# Mini_Multi_Function_Device.net
KiCad netlist of a schematic drawn in Altium Designer
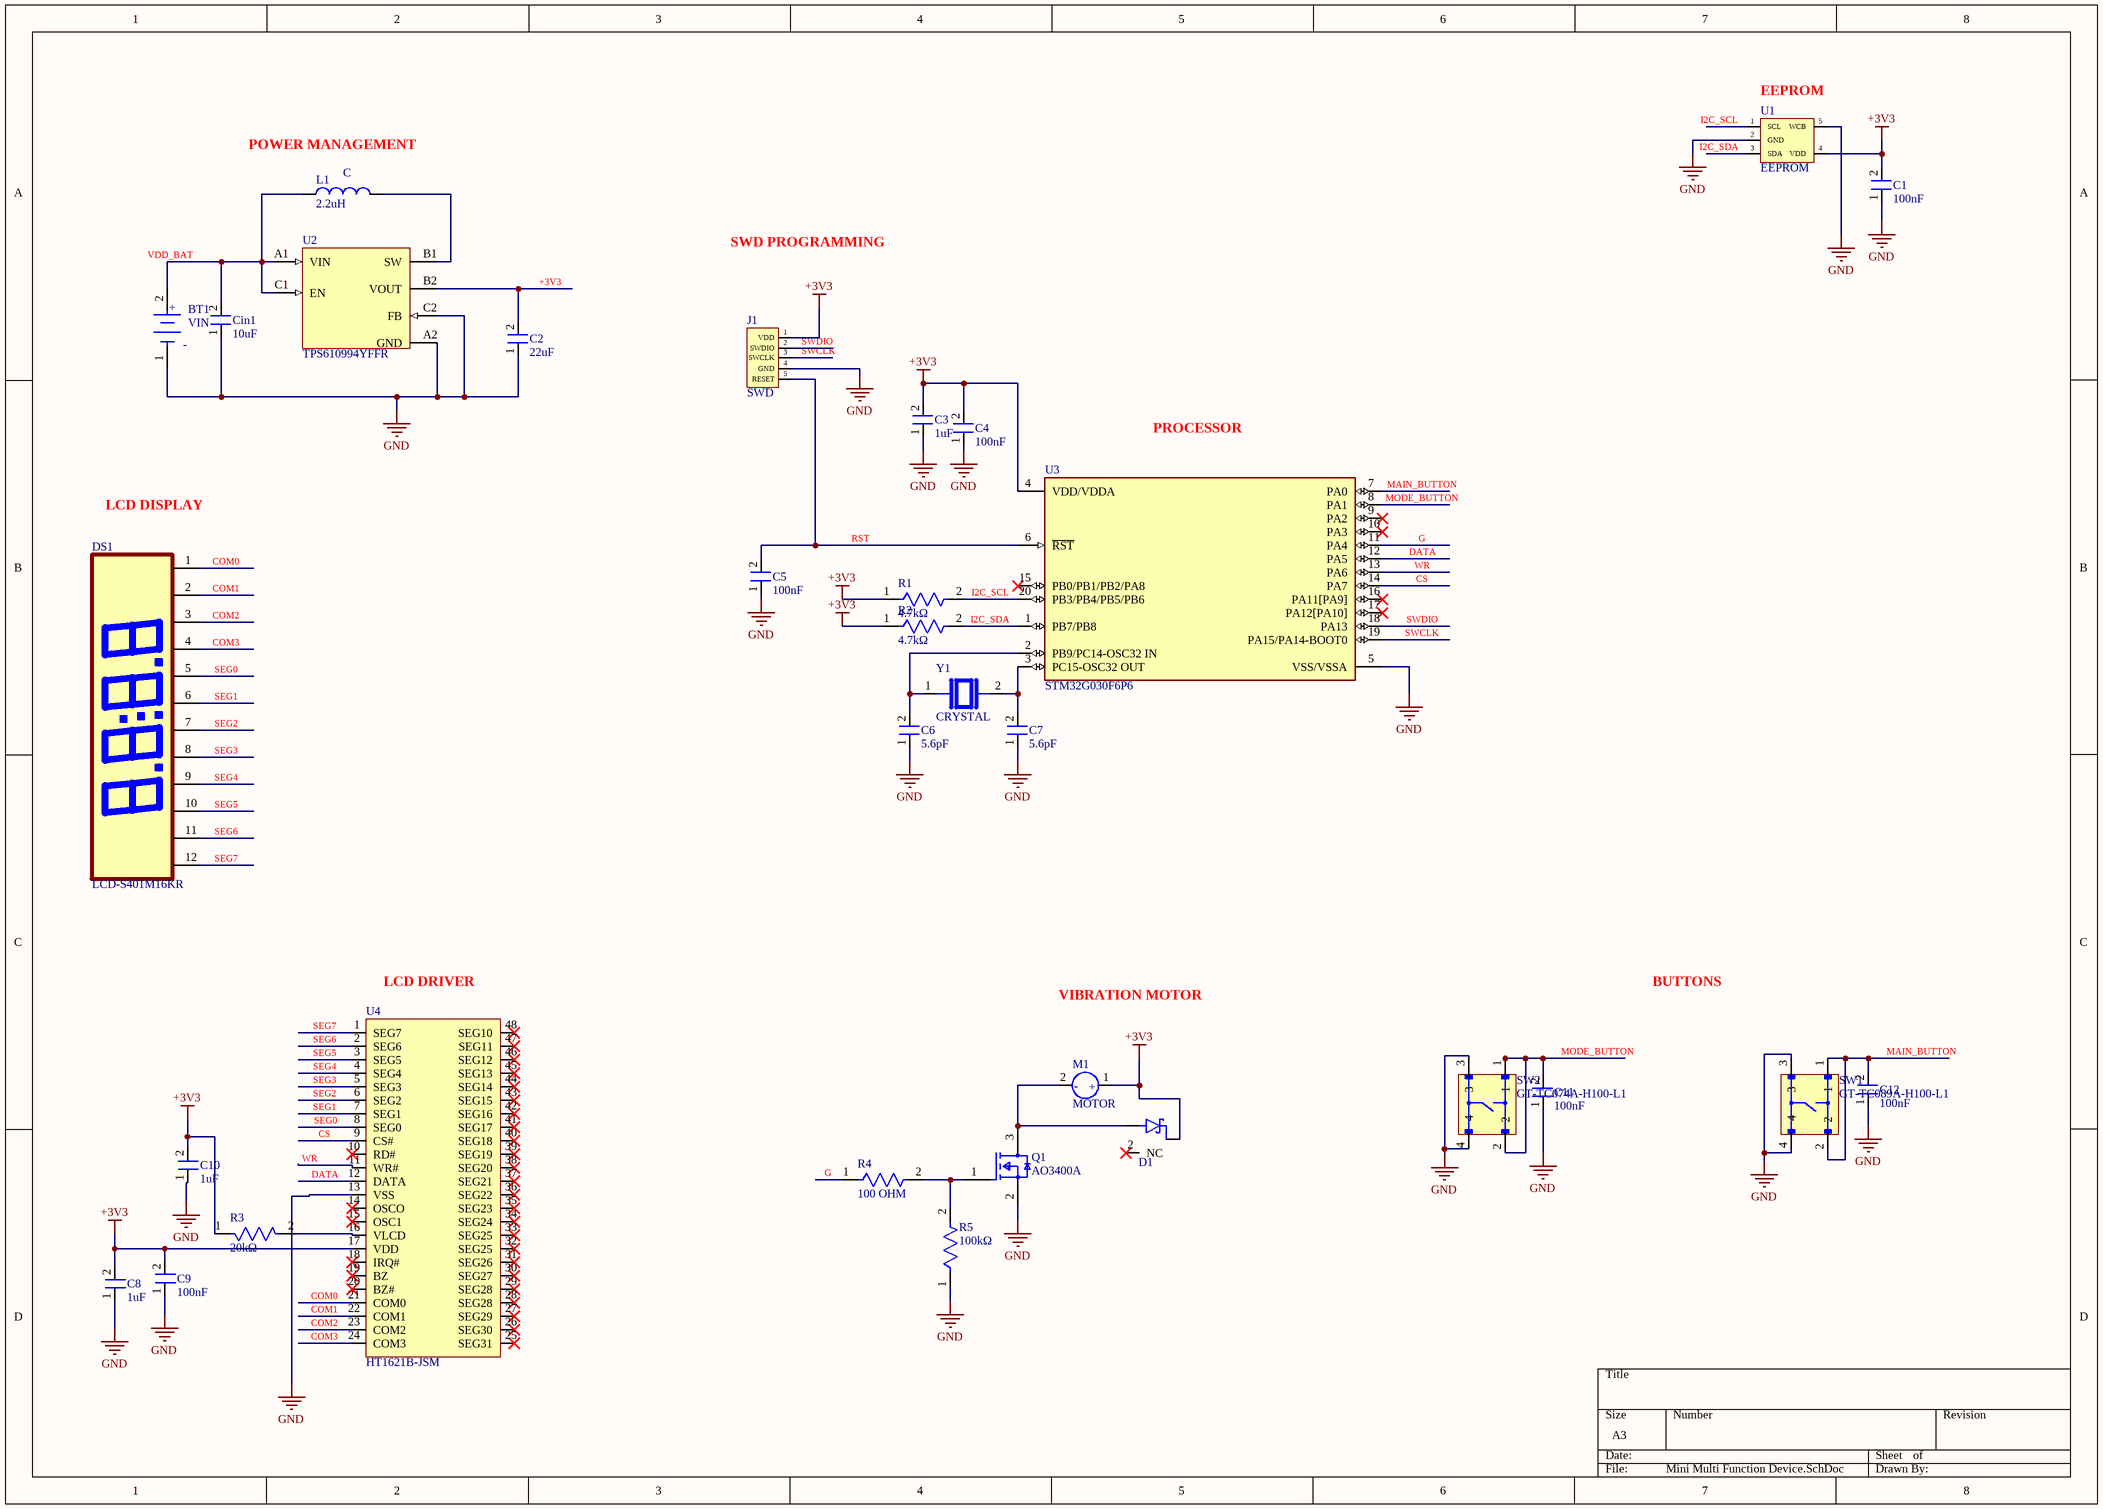
[diagram p0: Mini Multi Function Device.SchDoc]

(export (version "E")
  (design (tool "Eeschema 10.0.6"))
  (components
    (comp (ref "BT1")
      (value "VIN")
      (footprint "FP-3034-MFG")
      (description "Retainer 1 Button cell Ø20.0mm 2020，2025，2032 PCBinstall，SMD mount 4.06mm(height)")
      (fields (field (name "MANUFACTURER") "Keystone") (field (name "MANUFACTURER PART NUMBER") "3034"))
      (libsource (lib "Mini Multi Function Device") (part "3034"))
    )
    (comp (ref "C1")
      (value "100nF")
      (footprint "CAPACITOR")
      (description "Ceramic Capacitor, Ceramic, 10V, 5% +Tol, 5% -Tol, X5R, 15% TC, 0.1uF, Surface Mount, 0402")
      (fields
        (field (name "MANUFACTURER") "Yageo Group")
        (field (name "MANUFACTURER PART NUMBER") "CC0402JRX5R6BB104")
      )
      (libsource (lib "Mini Multi Function Device") (part "CC0402JRX5R6BB104"))
    )
    (comp (ref "C2")
      (value "22uF")
      (footprint "CAPACITOR_0805")
      (description "22uF 6.3V X5R ±20% 0805 Multilayer Ceramic Capacitors MLCC - SMD/SMT ROHS")
      (fields (field (name "LCSC PART") "C396739") (field (name "MANUFACTURER") "Walsin Tech Corp"))
      (libsource (lib "Mini Multi Function Device") (part "0805X226M6R3CT"))
    )
    (comp (ref "C3")
      (value "1uF")
      (footprint "CAPACITOR")
      (description "16V 1uF X5R 卤10% 0402 Multilayer Ceramic Capacitors MLCC - SMD/SMT ROHS")
      (fields
        (field (name "MANUFACTURER") "Samsung Electro-Mechanics")
        (field (name "MANUFACTURER PART NUMBER") "CL05A105KO5NNNC")
      )
      (libsource (lib "Mini Multi Function Device") (part "CL05A105KO5NNNC"))
    )
    (comp (ref "C4")
      (value "100nF")
      (footprint "CAPACITOR")
      (description "FCC0402B104K160AT 100nF ±10% 16V Ceramic Capacitor X7R 0402 Ceramic Capacitors  100nF   16V 10%")
      (fields (field (name "LCSC PART") "C5137468") (field (name "MANUFACTURER") "FOJAN"))
      (libsource (lib "Mini Multi Function Device") (part "FCC0402B104K160AT"))
    )
    (comp (ref "C5")
      (value "100nF")
      (footprint "CAPACITOR")
      (description "Ceramic Capacitor, Ceramic, 10V, 5% +Tol, 5% -Tol, X5R, 15% TC, 0.1uF, Surface Mount, 0402")
      (fields
        (field (name "MANUFACTURER") "Yageo Group")
        (field (name "MANUFACTURER PART NUMBER") "CC0402JRX5R6BB104")
      )
      (libsource (lib "Mini Multi Function Device") (part "CC0402JRX5R6BB104"))
    )
    (comp (ref "C6")
      (value "5.6pF")
      (footprint "CAPACITOR")
      (description "10V 5.6pF C0G 0402 Multilayer Ceramic Capacitors MLCC - SMD/SMT ROHS")
      (fields
        (field (name "LCSC PART") "C285041")
        (field (name "MANUFACTURER") "FH (Guangdong Fenghua Advanced Tech)")
      )
      (libsource (lib "Mini Multi Function Device") (part "0402CG5R6C100NT"))
    )
    (comp (ref "C7")
      (value "5.6pF")
      (footprint "CAPACITOR")
      (description "10V 5.6pF C0G 0402 Multilayer Ceramic Capacitors MLCC - SMD/SMT ROHS")
      (fields
        (field (name "LCSC PART") "C285041")
        (field (name "MANUFACTURER") "FH (Guangdong Fenghua Advanced Tech)")
      )
      (libsource (lib "Mini Multi Function Device") (part "0402CG5R6C100NT"))
    )
    (comp (ref "C8")
      (value "1uF")
      (footprint "CAPACITOR")
      (description "16V 1uF X5R 卤10% 0402 Multilayer Ceramic Capacitors MLCC - SMD/SMT ROHS")
      (fields
        (field (name "MANUFACTURER") "Samsung Electro-Mechanics")
        (field (name "MANUFACTURER PART NUMBER") "CL05A105KO5NNNC")
      )
      (libsource (lib "Mini Multi Function Device") (part "CL05A105KO5NNNC"))
    )
    (comp (ref "C9")
      (value "100nF")
      (footprint "CAPACITOR")
      (description "Ceramic Capacitor, Ceramic, 10V, 5% +Tol, 5% -Tol, X5R, 15% TC, 0.1uF, Surface Mount, 0402")
      (fields
        (field (name "MANUFACTURER") "Yageo Group")
        (field (name "MANUFACTURER PART NUMBER") "CC0402JRX5R6BB104")
      )
      (libsource (lib "Mini Multi Function Device") (part "CC0402JRX5R6BB104"))
    )
    (comp (ref "C10")
      (value "1uF")
      (footprint "CAPACITOR")
      (description "16V 1uF X5R 卤10% 0402 Multilayer Ceramic Capacitors MLCC - SMD/SMT ROHS")
      (fields
        (field (name "MANUFACTURER") "Samsung Electro-Mechanics")
        (field (name "MANUFACTURER PART NUMBER") "CL05A105KO5NNNC")
      )
      (libsource (lib "Mini Multi Function Device") (part "CL05A105KO5NNNC"))
    )
    (comp (ref "C11")
      (value "100nF")
      (footprint "CAPACITOR")
      (description "FCC0402B104K160AT 100nF ±10% 16V Ceramic Capacitor X7R 0402 Ceramic Capacitors  100nF   16V 10%")
      (fields (field (name "LCSC PART") "C5137468") (field (name "MANUFACTURER") "FOJAN"))
      (libsource (lib "Mini Multi Function Device") (part "FCC0402B104K160AT"))
    )
    (comp (ref "C12")
      (value "100nF")
      (footprint "CAPACITOR")
      (description "FCC0402B104K160AT 100nF ±10% 16V Ceramic Capacitor X7R 0402 Ceramic Capacitors  100nF   16V 10%")
      (fields (field (name "LCSC PART") "C5137468") (field (name "MANUFACTURER") "FOJAN"))
      (libsource (lib "Mini Multi Function Device") (part "FCC0402B104K160AT"))
    )
    (comp (ref "Cin1")
      (value "10uF")
      (footprint "CAPACITOR_0805")
      (description "10V 10uF X5R ±10% 0805 Multilayer Ceramic Capacitors MLCC - SMD/SMT ROHS")
      (fields (field (name "LCSC PART") "C77073") (field (name "MANUFACTURER") "Murata Electronics"))
      (libsource (lib "Mini Multi Function Device") (part "GRM21BR61A106KE19L"))
    )
    (comp (ref "D1")
      (value "BAT54")
      (footprint "SOT95P240X120-3N")
      (description "Diode Schottky 30V 0.2A Automotive 3-Pin SOT-23")
      (fields (field (name "MANUFACTURER") "Diodes Inc.") (field (name "LCSC PART") "C7528904"))
      (libsource (lib "Mini Multi Function Device") (part "BAT54"))
    )
    (comp (ref "DS1")
      (value "LCD-S401M16KR")
      (footprint "LCD-S401M16KR")
      (description "LCD Numeric Display Modules 4 Digit 0.17 7 Seg Reflective")
      (fields (field (name "MANUFACTURER") "Lumex") (field (name "LCSC PART") "C17355221"))
      (libsource (lib "Mini Multi Function Device") (part "LCD-S401M16KR"))
    )
    (comp (ref "J1")
      (value "SWD")
      (footprint "SWD_HEADER")
      (libsource (lib "Mini Multi Function Device") (part "SWD_HEADER"))
    )
    (comp (ref "L1")
      (value "2.2uH")
      (footprint "INDC2520X100N")
      (description "Inductor Power Chip Shielded Multi-Layer 2.2uH 20% 1MHz Ferrite 1.3A 0.1Ohm DCR 1008 T/R")
      (fields
        (field (name "MANUFACTURER") "Murata")
        (field (name "MANUFACTURER PART NUMBER") "LQM2HPN2R2MG0L")
      )
      (libsource (lib "Mini Multi Function Device") (part "LQM2HPN2R2MG0L"))
    )
    (comp (ref "M1")
      (value "MOTOR")
      (footprint "VCLP1020B002L")
      (description "Vibration Coin 3V Low Curr 0.75G")
      (fields
        (field (name "MANUFACTURER") "Vybronics")
        (field (name "MANUFACTURER PART NUMBER") "VCLP1020B002L")
      )
      (libsource (lib "Mini Multi Function Device") (part "VCLP1020B002L"))
    )
    (comp (ref "Q1")
      (value "AO3400A")
      (footprint "FP-SOT23-MFG")
      (description "Trans MOSFET N-CH 30V 5.7A 3-Pin SOT-23")
      (fields (field (name "MANUFACTURER") "Alpha & Omega Semiconductor") (field (name "LCSC PART") "C20917"))
      (libsource (lib "Mini Multi Function Device") (part "AO3400A"))
    )
    (comp (ref "R1")
      (value "4.7kΩ")
      (footprint "RESISTOR")
      (description "-55℃~+125℃ 30V 4.7kΩ 62.5mW ±5% ±50ppm/℃ 0402 Chip Resistor - Surface Mount ROHS")
      (fields (field (name "LCSC PART") "C54974059") (field (name "MANUFACTURER") "SIE"))
      (libsource (lib "Mini Multi Function Device") (part "CRF0402R472JN"))
    )
    (comp (ref "R2")
      (value "4.7kΩ")
      (footprint "RESISTOR")
      (description "-55℃~+125℃ 30V 4.7kΩ 62.5mW ±5% ±50ppm/℃ 0402 Chip Resistor - Surface Mount ROHS")
      (fields (field (name "LCSC PART") "C54974059") (field (name "MANUFACTURER") "SIE"))
      (libsource (lib "Mini Multi Function Device") (part "CRF0402R472JN"))
    )
    (comp (ref "R3")
      (value "20kΩ")
      (footprint "RESISTOR")
      (fields
        (field (name "LCSC PART") "C319759")
        (field (name "MANUFACTURER") "Viking Tech")
        (field (name "MANUFACTURER PART NUMBER") "AR02DTD2002")
      )
      (libsource (lib "Mini Multi Function Device") (part "AR02DTD2002"))
    )
    (comp (ref "R4")
      (value "100 OHM")
      (footprint "RESISTOR")
      (description "Res Thick Film 0402 100 Ohm 5% 0.063W(1/16W) ±100ppm/C Pad SMD T/R Automotive AEC-Q200")
      (fields
        (field (name "MANUFACTURER") "Yageo Group")
        (field (name "MANUFACTURER PART NUMBER") "AC0402JR-07100RL")
      )
      (libsource (lib "Mini Multi Function Device") (part "AC0402JR-07100RL"))
    )
    (comp (ref "R5")
      (value "100kΩ")
      (footprint "RESISTOR")
      (description "62.5mW Thick Film Resistors 50V ±100ppm/℃ ±5% 100kΩ 0402 Chip Resistor - Surface Mount ROHS")
      (fields
        (field (name "MANUFACTURER") "Yageo Group")
        (field (name "MANUFACTURER PART NUMBER") "RC0402JR-07100KL")
      )
      (libsource (lib "Mini Multi Function Device") (part "RC0402JR-07100KL"))
    )
    (comp (ref "SW1")
      (value "GT-TC089A-H100-L1")
      (footprint "SW-SMD_4P-L6.0-W6.0-P4.50-LS8.5")
      (fields (field (name "LCSC PART") "C843652") (field (name "MANUFACTURER") "G-Switch"))
      (libsource (lib "Mini Multi Function Device") (part "GT-TC089A-H100-L1"))
    )
    (comp (ref "SW2")
      (value "GT-TC074A-H100-L1")
      (footprint "SW-SMD_4P-L4.5-W4.5-P3.00-LS7.5")
      (fields (field (name "LCSC PART") "C963232") (field (name "MANUFACTURER") "G-Switch"))
      (libsource (lib "Mini Multi Function Device") (part "GT-TC074A-H100-L1"))
    )
    (comp (ref "U1")
      (value "EEPROM")
      (footprint "AT24C02C-STUM-TQN")
      (description "SOT-23-5 EEPROM ROHS")
      (fields (field (name "LCSC PART") "C53432858") (field (name "MANUFACTURER") "QNH"))
      (libsource (lib "Mini Multi Function Device") (part "AT24C02C-STUM-TQN"))
    )
    (comp (ref "U2")
      (value "TPS610994YFFR")
      (footprint "BGA6N40P3X2_122X88X62N")
      (description "0.7Vin Synchronous Boost Converter with 800 nA Ultra-Low Quiescent Current 6-DSBGA -40 to 85")
      (fields (field (name "MANUFACTURER") "Texas Instruments") (field (name "LCSC PART") "C2650335"))
      (libsource (lib "Mini Multi Function Device") (part "TPS610994YFFR"))
    )
    (comp (ref "U3")
      (value "STM32G030F6P6")
      (footprint "FP-TSSOP20-YA-MFG")
      (description "Microcontroller 32-bit ARM Cortex-M0+ RISC 32KB Flash 3.3V 20-Pin TSSOP Tray")
      (fields (field (name "MANUFACTURER") "STMicroelectronics") (field (name "LCSC PART") "C724040"))
      (libsource (lib "Mini Multi Function Device") (part "STM32G030F6P6"))
    )
    (comp (ref "U4")
      (value "HT1621B-JSM")
      (footprint "HT1621B-JSM")
      (fields (field (name "LCSC PART") "C18190086") (field (name "MANUFACTURER") "JSMSEMI"))
      (libsource (lib "Mini Multi Function Device") (part "HT1621B-JSM"))
    )
    (comp (ref "Y1")
      (value "CRYSTAL")
      (footprint "OSC-SMD_L3.2-W1.5")
      (description "-40℃~+85℃ 12.5pF 32.768kHz 70kΩ SMD crystal oscillator ±20ppm ±30ppm SMD3215-2P Crystals ROHS")
      (fields (field (name "LCSC PART") "C620155") (field (name "MANUFACTURER") "YXC Crystal Oscillators"))
      (libsource (lib "Mini Multi Function Device") (part "X321532768KGD2SI"))
    )
  )
  (nets
    (net (code "1") (name "+3V3") (class "Default")
      (node (ref "C1") (pin "2") (pinfunction "3_2") (pintype "passive"))
      (node (ref "C10") (pin "2") (pinfunction "3_2") (pintype "passive"))
      (node (ref "C2") (pin "2") (pinfunction "3_2") (pintype "passive"))
      (node (ref "C3") (pin "2") (pinfunction "3_2") (pintype "passive"))
      (node (ref "C4") (pin "2") (pinfunction "3_2") (pintype "passive"))
      (node (ref "C8") (pin "2") (pinfunction "3_2") (pintype "passive"))
      (node (ref "C9") (pin "2") (pinfunction "3_2") (pintype "passive"))
      (node (ref "D1") (pin "3") (pinfunction "3_3") (pintype "passive"))
      (node (ref "J1") (pin "1") (pinfunction "VDD_1") (pintype "passive"))
      (node (ref "M1") (pin "1") (pinfunction "1_1") (pintype "passive"))
      (node (ref "R1") (pin "1") (pinfunction "1_1") (pintype "passive"))
      (node (ref "R2") (pin "1") (pinfunction "1_1") (pintype "passive"))
      (node (ref "R3") (pin "1") (pinfunction "1_1") (pintype "passive"))
      (node (ref "U1") (pin "4") (pinfunction "VDD_4") (pintype "passive"))
      (node (ref "U2") (pin "B2") (pinfunction "VOUT_B2") (pintype "passive"))
      (node (ref "U3") (pin "4") (pinfunction "VDD/VDDA_4") (pintype "power_in"))
      (node (ref "U4") (pin "17") (pinfunction "VDD_17") (pintype "open_collector"))
    )
    (net (code "2") (name "/COM0") (class "Default")
      (node (ref "DS1") (pin "1") (pinfunction "P$1_1") (pintype "passive"))
      (node (ref "U4") (pin "21") (pinfunction "COM0_21") (pintype "open_collector"))
    )
    (net (code "3") (name "/COM1") (class "Default")
      (node (ref "DS1") (pin "2") (pinfunction "P$2_2") (pintype "passive"))
      (node (ref "U4") (pin "22") (pinfunction "COM1_22") (pintype "open_collector"))
    )
    (net (code "4") (name "/COM2") (class "Default")
      (node (ref "DS1") (pin "3") (pinfunction "P$3_3") (pintype "passive"))
      (node (ref "U4") (pin "23") (pinfunction "COM2_23") (pintype "open_collector"))
    )
    (net (code "5") (name "/COM3") (class "Default")
      (node (ref "DS1") (pin "4") (pinfunction "P$4_4") (pintype "passive"))
      (node (ref "U4") (pin "24") (pinfunction "COM3_24") (pintype "open_collector"))
    )
    (net (code "6") (name "/CS") (class "Default")
      (node (ref "U3") (pin "14") (pinfunction "PA7_14") (pintype "bidirectional"))
      (node (ref "U4") (pin "9") (pinfunction "CS#_9") (pintype "open_collector"))
    )
    (net (code "7") (name "/DATA") (class "Default")
      (node (ref "U3") (pin "12") (pinfunction "PA5_12") (pintype "bidirectional"))
      (node (ref "U4") (pin "12") (pinfunction "DATA_12") (pintype "open_collector"))
    )
    (net (code "8") (name "/G") (class "Default")
      (node (ref "R4") (pin "1") (pinfunction "1_1") (pintype "passive"))
      (node (ref "U3") (pin "11") (pinfunction "PA4_11") (pintype "bidirectional"))
    )
    (net (code "9") (name "/I2C_SCL") (class "Default")
      (node (ref "R1") (pin "2") (pinfunction "2_2") (pintype "passive"))
      (node (ref "U1") (pin "1") (pinfunction "SCL_1") (pintype "passive"))
      (node (ref "U3") (pin "20") (pinfunction "PB3/PB4/PB5/PB6_20") (pintype "bidirectional"))
    )
    (net (code "10") (name "/I2C_SDA") (class "Default")
      (node (ref "R2") (pin "2") (pinfunction "2_2") (pintype "passive"))
      (node (ref "U1") (pin "3") (pinfunction "SDA_3") (pintype "passive"))
      (node (ref "U3") (pin "1") (pinfunction "PB7/PB8_1") (pintype "bidirectional"))
    )
    (net (code "11") (name "/MAIN_BUTTON") (class "Default")
      (node (ref "C12") (pin "2") (pinfunction "3_2") (pintype "passive"))
      (node (ref "SW1") (pin "1") (pinfunction "1_1") (pintype "passive"))
      (node (ref "SW1") (pin "2") (pinfunction "2_2") (pintype "passive"))
      (node (ref "U3") (pin "7") (pinfunction "PA0_7") (pintype "bidirectional"))
    )
    (net (code "12") (name "/MODE_BUTTON") (class "Default")
      (node (ref "C11") (pin "2") (pinfunction "3_2") (pintype "passive"))
      (node (ref "SW2") (pin "1") (pinfunction "1_1") (pintype "passive"))
      (node (ref "SW2") (pin "2") (pinfunction "2_2") (pintype "passive"))
      (node (ref "U3") (pin "8") (pinfunction "PA1_8") (pintype "bidirectional"))
    )
    (net (code "13") (name "/RST") (class "Default")
      (node (ref "C5") (pin "2") (pinfunction "3_2") (pintype "passive"))
      (node (ref "J1") (pin "5") (pinfunction "RESET_5") (pintype "passive"))
      (node (ref "U3") (pin "6") (pinfunction "~{RST}_6") (pintype "input"))
    )
    (net (code "14") (name "/SEG0") (class "Default")
      (node (ref "DS1") (pin "5") (pinfunction "P$5_5") (pintype "passive"))
      (node (ref "U4") (pin "8") (pinfunction "SEG0_8") (pintype "open_collector"))
    )
    (net (code "15") (name "/SEG1") (class "Default")
      (node (ref "DS1") (pin "6") (pinfunction "P$6_6") (pintype "passive"))
      (node (ref "U4") (pin "7") (pinfunction "SEG1_7") (pintype "open_collector"))
    )
    (net (code "16") (name "/SEG2") (class "Default")
      (node (ref "DS1") (pin "7") (pinfunction "P$7_7") (pintype "passive"))
      (node (ref "U4") (pin "6") (pinfunction "SEG2_6") (pintype "open_collector"))
    )
    (net (code "17") (name "/SEG3") (class "Default")
      (node (ref "DS1") (pin "8") (pinfunction "P$8_8") (pintype "passive"))
      (node (ref "U4") (pin "5") (pinfunction "SEG3_5") (pintype "open_collector"))
    )
    (net (code "18") (name "/SEG4") (class "Default")
      (node (ref "DS1") (pin "9") (pinfunction "P$9_9") (pintype "passive"))
      (node (ref "U4") (pin "4") (pinfunction "SEG4_4") (pintype "open_collector"))
    )
    (net (code "19") (name "/SEG5") (class "Default")
      (node (ref "DS1") (pin "10") (pinfunction "P$10_10") (pintype "passive"))
      (node (ref "U4") (pin "3") (pinfunction "SEG5_3") (pintype "open_collector"))
    )
    (net (code "20") (name "/SEG6") (class "Default")
      (node (ref "DS1") (pin "11") (pinfunction "P$11_11") (pintype "passive"))
      (node (ref "U4") (pin "2") (pinfunction "SEG6_2") (pintype "open_collector"))
    )
    (net (code "21") (name "/SEG7") (class "Default")
      (node (ref "DS1") (pin "12") (pinfunction "P$12_12") (pintype "passive"))
      (node (ref "U4") (pin "1") (pinfunction "SEG7_1") (pintype "open_collector"))
    )
    (net (code "22") (name "/SWCLK") (class "Default")
      (node (ref "J1") (pin "3") (pinfunction "SWCLK_3") (pintype "passive"))
      (node (ref "U3") (pin "19") (pinfunction "PA15/PA14-BOOT0_19") (pintype "bidirectional"))
    )
    (net (code "23") (name "/SWDIO") (class "Default")
      (node (ref "J1") (pin "2") (pinfunction "SWDIO_2") (pintype "passive"))
      (node (ref "U3") (pin "18") (pinfunction "PA13_18") (pintype "bidirectional"))
    )
    (net (code "24") (name "/VDD_BAT") (class "Default")
      (node (ref "BT1") (pin "2") (pinfunction "A_2") (pintype "passive"))
      (node (ref "Cin1") (pin "2") (pinfunction "3_2") (pintype "passive"))
      (node (ref "L1") (pin "1") (pinfunction "1_1") (pintype "passive"))
      (node (ref "U2") (pin "A1") (pinfunction "VIN_A1") (pintype "input"))
      (node (ref "U2") (pin "C1") (pinfunction "EN_C1") (pintype "input"))
    )
    (net (code "25") (name "/WR") (class "Default")
      (node (ref "U3") (pin "13") (pinfunction "PA6_13") (pintype "bidirectional"))
      (node (ref "U4") (pin "11") (pinfunction "WR#_11") (pintype "open_collector"))
    )
    (net (code "26") (name "GND") (class "Default")
      (node (ref "BT1") (pin "1") (pinfunction "C_1") (pintype "passive"))
      (node (ref "C1") (pin "1") (pinfunction "2_1") (pintype "passive"))
      (node (ref "C10") (pin "1") (pinfunction "2_1") (pintype "passive"))
      (node (ref "C11") (pin "1") (pinfunction "2_1") (pintype "passive"))
      (node (ref "C12") (pin "1") (pinfunction "2_1") (pintype "passive"))
      (node (ref "C2") (pin "1") (pinfunction "2_1") (pintype "passive"))
      (node (ref "C3") (pin "1") (pinfunction "2_1") (pintype "passive"))
      (node (ref "C4") (pin "1") (pinfunction "2_1") (pintype "passive"))
      (node (ref "C5") (pin "1") (pinfunction "2_1") (pintype "passive"))
      (node (ref "C6") (pin "1") (pinfunction "2_1") (pintype "passive"))
      (node (ref "C7") (pin "1") (pinfunction "2_1") (pintype "passive"))
      (node (ref "C8") (pin "1") (pinfunction "2_1") (pintype "passive"))
      (node (ref "C9") (pin "1") (pinfunction "2_1") (pintype "passive"))
      (node (ref "Cin1") (pin "1") (pinfunction "2_1") (pintype "passive"))
      (node (ref "J1") (pin "4") (pinfunction "GND_4") (pintype "passive"))
      (node (ref "Q1") (pin "2") (pinfunction "S_2") (pintype "passive"))
      (node (ref "R5") (pin "1") (pinfunction "1_1") (pintype "passive"))
      (node (ref "SW1") (pin "3") (pinfunction "3_3") (pintype "passive"))
      (node (ref "SW1") (pin "4") (pinfunction "4_4") (pintype "passive"))
      (node (ref "SW2") (pin "3") (pinfunction "3_3") (pintype "passive"))
      (node (ref "SW2") (pin "4") (pinfunction "4_4") (pintype "passive"))
      (node (ref "U1") (pin "2") (pinfunction "GND_2") (pintype "passive"))
      (node (ref "U1") (pin "5") (pinfunction "WCB_5") (pintype "passive"))
      (node (ref "U2") (pin "A2") (pinfunction "GND_A2") (pintype "power_in"))
      (node (ref "U2") (pin "C2") (pinfunction "FB_C2") (pintype "input"))
      (node (ref "U3") (pin "5") (pinfunction "VSS/VSSA_5") (pintype "power_in"))
      (node (ref "U4") (pin "13") (pinfunction "VSS_13") (pintype "open_collector"))
    )
    (net (code "27") (name "Net-(C6-3)") (class "Default")
      (node (ref "C6") (pin "2") (pinfunction "3_2") (pintype "passive"))
      (node (ref "U3") (pin "2") (pinfunction "PB9/PC14-OSC32_IN_2") (pintype "bidirectional"))
      (node (ref "Y1") (pin "1") (pinfunction "1_1") (pintype "passive"))
    )
    (net (code "28") (name "Net-(C7-3)") (class "Default")
      (node (ref "C7") (pin "2") (pinfunction "3_2") (pintype "passive"))
      (node (ref "U3") (pin "3") (pinfunction "PC15-OSC32_OUT_3") (pintype "bidirectional"))
      (node (ref "Y1") (pin "2") (pinfunction "2_2") (pintype "passive"))
    )
    (net (code "29") (name "Net-(Q1-D)") (class "Default")
      (node (ref "D1") (pin "1") (pinfunction "1_1") (pintype "passive"))
      (node (ref "M1") (pin "2") (pinfunction "2_2") (pintype "passive"))
      (node (ref "Q1") (pin "3") (pinfunction "D_3") (pintype "passive"))
    )
    (net (code "30") (name "Net-(Q1-G)") (class "Default")
      (node (ref "Q1") (pin "1") (pinfunction "G_1") (pintype "passive"))
      (node (ref "R4") (pin "2") (pinfunction "2_2") (pintype "passive"))
      (node (ref "R5") (pin "2") (pinfunction "2_2") (pintype "passive"))
    )
    (net (code "31") (name "Net-(U2-SW)") (class "Default")
      (node (ref "L1") (pin "2") (pinfunction "2_2") (pintype "passive"))
      (node (ref "U2") (pin "B1") (pinfunction "SW_B1") (pintype "passive"))
    )
    (net (code "32") (name "Net-(U4-VLCD)") (class "Default")
      (node (ref "R3") (pin "2") (pinfunction "2_2") (pintype "passive"))
      (node (ref "U4") (pin "16") (pinfunction "VLCD_16") (pintype "open_collector"))
    )
    (net (code "33") (name "unconnected-(D1-NC-Pad2)") (class "Default")
      (node (ref "D1") (pin "2") (pinfunction "NC_2") (pintype "passive+no_connect"))
    )
    (net (code "34") (name "unconnected-(U3-PA2-Pad9)") (class "Default")
      (node (ref "U3") (pin "9") (pinfunction "PA2_9") (pintype "bidirectional+no_connect"))
    )
    (net (code "35") (name "unconnected-(U3-PA3-Pad10)") (class "Default")
      (node (ref "U3") (pin "10") (pinfunction "PA3_10") (pintype "bidirectional+no_connect"))
    )
    (net (code "36") (name "unconnected-(U3-PA11[PA9]-Pad16)") (class "Default")
      (node (ref "U3") (pin "16") (pinfunction "PA11[PA9]_16") (pintype "bidirectional+no_connect"))
    )
    (net (code "37") (name "unconnected-(U3-PA12[PA10]-Pad17)") (class "Default")
      (node (ref "U3") (pin "17") (pinfunction "PA12[PA10]_17") (pintype "bidirectional+no_connect"))
    )
    (net (code "38") (name "unconnected-(U3-PB0{slash}PB1{slash}PB2{slash}PA8-Pad15)") (class "Default")
      (node (ref "U3") (pin "15") (pinfunction "PB0/PB1/PB2/PA8_15") (pintype "bidirectional+no_connect"))
    )
    (net (code "39") (name "unconnected-(U4-BZ#-Pad20)") (class "Default")
      (node (ref "U4") (pin "20") (pinfunction "BZ#_20") (pintype "open_collector+no_connect"))
    )
    (net (code "40") (name "unconnected-(U4-BZ-Pad19)") (class "Default")
      (node (ref "U4") (pin "19") (pinfunction "BZ_19") (pintype "open_collector+no_connect"))
    )
    (net (code "41") (name "unconnected-(U4-IRQ#-Pad18)") (class "Default")
      (node (ref "U4") (pin "18") (pinfunction "IRQ#_18") (pintype "open_collector+no_connect"))
    )
    (net (code "42") (name "unconnected-(U4-OSC1-Pad15)") (class "Default")
      (node (ref "U4") (pin "15") (pinfunction "OSC1_15") (pintype "open_collector+no_connect"))
    )
    (net (code "43") (name "unconnected-(U4-OSCO-Pad14)") (class "Default")
      (node (ref "U4") (pin "14") (pinfunction "OSCO_14") (pintype "open_collector+no_connect"))
    )
    (net (code "44") (name "unconnected-(U4-RD#-Pad10)") (class "Default")
      (node (ref "U4") (pin "10") (pinfunction "RD#_10") (pintype "open_collector+no_connect"))
    )
    (net (code "45") (name "unconnected-(U4-SEG10-Pad48)") (class "Default")
      (node (ref "U4") (pin "48") (pinfunction "SEG10_48") (pintype "open_collector+no_connect"))
    )
    (net (code "46") (name "unconnected-(U4-SEG11-Pad47)") (class "Default")
      (node (ref "U4") (pin "47") (pinfunction "SEG11_47") (pintype "open_collector+no_connect"))
    )
    (net (code "47") (name "unconnected-(U4-SEG12-Pad46)") (class "Default")
      (node (ref "U4") (pin "46") (pinfunction "SEG12_46") (pintype "open_collector+no_connect"))
    )
    (net (code "48") (name "unconnected-(U4-SEG13-Pad45)") (class "Default")
      (node (ref "U4") (pin "45") (pinfunction "SEG13_45") (pintype "open_collector+no_connect"))
    )
    (net (code "49") (name "unconnected-(U4-SEG14-Pad44)") (class "Default")
      (node (ref "U4") (pin "44") (pinfunction "SEG14_44") (pintype "open_collector+no_connect"))
    )
    (net (code "50") (name "unconnected-(U4-SEG15-Pad43)") (class "Default")
      (node (ref "U4") (pin "43") (pinfunction "SEG15_43") (pintype "open_collector+no_connect"))
    )
    (net (code "51") (name "unconnected-(U4-SEG16-Pad42)") (class "Default")
      (node (ref "U4") (pin "42") (pinfunction "SEG16_42") (pintype "open_collector+no_connect"))
    )
    (net (code "52") (name "unconnected-(U4-SEG17-Pad41)") (class "Default")
      (node (ref "U4") (pin "41") (pinfunction "SEG17_41") (pintype "open_collector+no_connect"))
    )
    (net (code "53") (name "unconnected-(U4-SEG18-Pad40)") (class "Default")
      (node (ref "U4") (pin "40") (pinfunction "SEG18_40") (pintype "open_collector+no_connect"))
    )
    (net (code "54") (name "unconnected-(U4-SEG19-Pad39)") (class "Default")
      (node (ref "U4") (pin "39") (pinfunction "SEG19_39") (pintype "open_collector+no_connect"))
    )
    (net (code "55") (name "unconnected-(U4-SEG20-Pad38)") (class "Default")
      (node (ref "U4") (pin "38") (pinfunction "SEG20_38") (pintype "open_collector+no_connect"))
    )
    (net (code "56") (name "unconnected-(U4-SEG21-Pad37)") (class "Default")
      (node (ref "U4") (pin "37") (pinfunction "SEG21_37") (pintype "open_collector+no_connect"))
    )
    (net (code "57") (name "unconnected-(U4-SEG22-Pad36)") (class "Default")
      (node (ref "U4") (pin "36") (pinfunction "SEG22_36") (pintype "open_collector+no_connect"))
    )
    (net (code "58") (name "unconnected-(U4-SEG23-Pad35)") (class "Default")
      (node (ref "U4") (pin "35") (pinfunction "SEG23_35") (pintype "open_collector+no_connect"))
    )
    (net (code "59") (name "unconnected-(U4-SEG24-Pad34)") (class "Default")
      (node (ref "U4") (pin "34") (pinfunction "SEG24_34") (pintype "open_collector+no_connect"))
    )
    (net (code "60") (name "unconnected-(U4-SEG25-Pad32)") (class "Default")
      (node (ref "U4") (pin "32") (pinfunction "SEG25_32") (pintype "open_collector+no_connect"))
    )
    (net (code "61") (name "unconnected-(U4-SEG25-Pad33)") (class "Default")
      (node (ref "U4") (pin "33") (pinfunction "SEG25_33") (pintype "open_collector+no_connect"))
    )
    (net (code "62") (name "unconnected-(U4-SEG26-Pad31)") (class "Default")
      (node (ref "U4") (pin "31") (pinfunction "SEG26_31") (pintype "open_collector+no_connect"))
    )
    (net (code "63") (name "unconnected-(U4-SEG27-Pad30)") (class "Default")
      (node (ref "U4") (pin "30") (pinfunction "SEG27_30") (pintype "open_collector+no_connect"))
    )
    (net (code "64") (name "unconnected-(U4-SEG28-Pad28)") (class "Default")
      (node (ref "U4") (pin "28") (pinfunction "SEG28_28") (pintype "open_collector+no_connect"))
    )
    (net (code "65") (name "unconnected-(U4-SEG28-Pad29)") (class "Default")
      (node (ref "U4") (pin "29") (pinfunction "SEG28_29") (pintype "open_collector+no_connect"))
    )
    (net (code "66") (name "unconnected-(U4-SEG29-Pad27)") (class "Default")
      (node (ref "U4") (pin "27") (pinfunction "SEG29_27") (pintype "open_collector+no_connect"))
    )
    (net (code "67") (name "unconnected-(U4-SEG30-Pad26)") (class "Default")
      (node (ref "U4") (pin "26") (pinfunction "SEG30_26") (pintype "open_collector+no_connect"))
    )
    (net (code "68") (name "unconnected-(U4-SEG31-Pad25)") (class "Default")
      (node (ref "U4") (pin "25") (pinfunction "SEG31_25") (pintype "open_collector+no_connect"))
    )
  )
)
